# bf.net
KiCad netlist of a schematic drawn in EAGLE
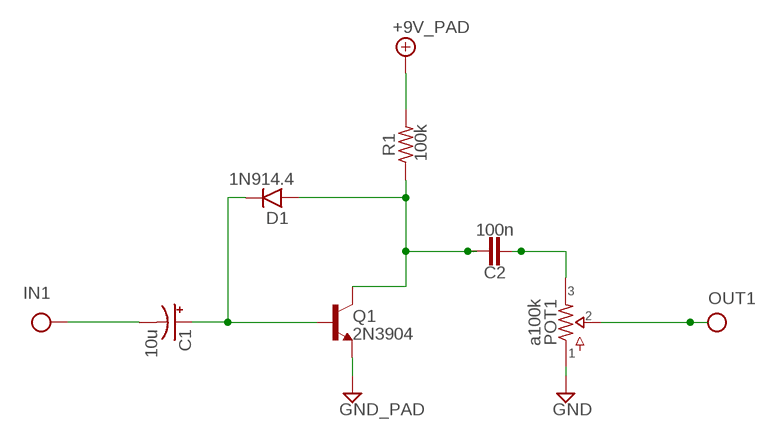
[diagram p0: schematic, sheet 1]

(export (version "E")
  (design (tool "Eeschema 10.0.6"))
  (components
    (comp (ref "C1")
      (value "10u")
      (footprint "eagle-import:050_020")
      (libsource (lib "eagle-import") (part "050"))
    )
    (comp (ref "C2")
      (value "100n")
      (footprint "eagle-import:0.2_.SML")
      (libsource (lib "eagle-import") (part "CAP.2"))
    )
    (comp (ref "D1")
      (value "1N914.4")
      (footprint "eagle-import:DO35-4")
      (libsource (lib "eagle-import") (part "1N914.4"))
    )
    (comp (ref "GND2")
      (value "GND_PAD")
      (footprint "eagle-import:SQUARE")
      (libsource (lib "eagle-import") (part "GND_PAD"))
    )
    (comp (ref "IN1")
      (value "IN")
      (footprint "eagle-import:SQUARE")
      (libsource (lib "eagle-import") (part "IN"))
    )
    (comp (ref "OUT1")
      (value "OUT")
      (footprint "eagle-import:SQUARE")
      (libsource (lib "eagle-import") (part "OUT"))
    )
    (comp (ref "POT1")
      (value "a100k")
      (footprint "eagle-import:16MM_B.MOUNT")
      (libsource (lib "eagle-import") (part "16MM.1"))
    )
    (comp (ref "Q1")
      (value "2N3904")
      (footprint "eagle-import:TO92-")
      (libsource (lib "eagle-import") (part "2N3904"))
    )
    (comp (ref "R1")
      (value "100k")
      (footprint "eagle-import:R0207_4")
      (libsource (lib "eagle-import") (part "RESISTORS.4"))
    )
    (comp (ref "V1")
      (value "+9V_PAD")
      (footprint "eagle-import:SQUARE")
      (libsource (lib "eagle-import") (part "+9V_PAD"))
    )
  )
  (nets
    (net (code "1") (name "+9V_PAD") (class "Default")
      (node (ref "R1") (pin "2") (pinfunction "2_2") (pintype "passive"))
      (node (ref "V1") (pin "1") (pinfunction "+9V_1") (pintype "power_in"))
    )
    (net (code "2") (name "GND") (class "Default")
      (node (ref "GND2") (pin "1") (pinfunction "GND_1") (pintype "power_in"))
      (node (ref "POT1") (pin "1") (pinfunction "1_1") (pintype "passive"))
      (node (ref "Q1") (pin "3") (pinfunction "E_3") (pintype "passive"))
    )
    (net (code "3") (name "IN") (class "Default")
      (node (ref "C1") (pin "-") (pinfunction "-_-") (pintype "passive"))
      (node (ref "IN1") (pin "1") (pinfunction "IN_1") (pintype "power_in"))
    )
    (net (code "4") (name "Net-(C2-Pad2)") (class "Default")
      (node (ref "C2") (pin "2") (pinfunction "2_2") (pintype "passive"))
      (node (ref "POT1") (pin "3") (pinfunction "3_3") (pintype "passive"))
    )
    (net (code "5") (name "Net-(Q1-B)") (class "Default")
      (node (ref "C1") (pin "+") (pinfunction "+_+") (pintype "passive"))
      (node (ref "D1") (pin "C") (pinfunction "C_C") (pintype "passive"))
      (node (ref "Q1") (pin "2") (pinfunction "B_2") (pintype "passive"))
    )
    (net (code "6") (name "Net-(Q1-C)") (class "Default")
      (node (ref "C2") (pin "1") (pinfunction "1_1") (pintype "passive"))
      (node (ref "D1") (pin "A") (pinfunction "A_A") (pintype "passive"))
      (node (ref "Q1") (pin "1") (pinfunction "C_1") (pintype "passive"))
      (node (ref "R1") (pin "1") (pinfunction "1_1") (pintype "passive"))
    )
    (net (code "7") (name "OUT") (class "Default")
      (node (ref "OUT1") (pin "1") (pinfunction "OUT_1") (pintype "power_in"))
      (node (ref "POT1") (pin "2") (pinfunction "2_2") (pintype "passive"))
    )
  )
)
